# Kinen_Port.net
KiCad netlist of a schematic drawn in Altium Designer
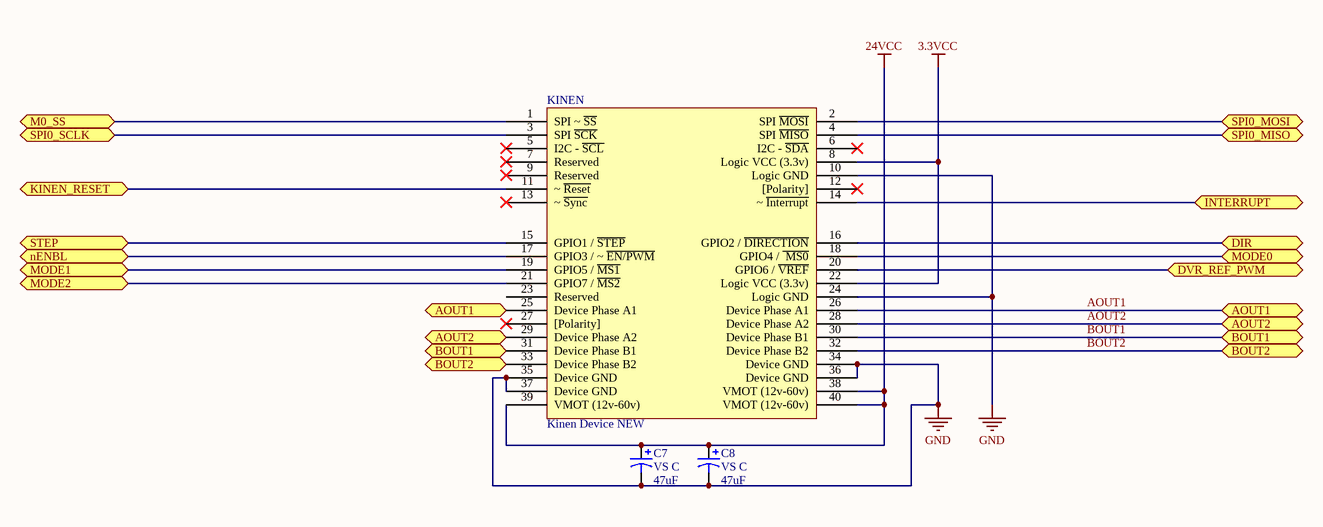
[diagram p0: Kinen Port.SchDoc]

(export (version "E")
  (design (tool "Eeschema 10.0.6"))
  (components
    (comp (ref "C7")
      (value "VS C")
      (footprint "Panasonic VS C")
      (description "Polarized Capacitor (Radial)")
      (fields (field (name "ALTIUM_VALUE") "47uF") (field (name "PUBLISHER") "Altium Limited"))
      (libsource (lib "Miscellaneous Devices") (part "Cap Pol1"))
    )
    (comp (ref "C8")
      (value "VS C")
      (footprint "Panasonic VS C")
      (description "Polarized Capacitor (Radial)")
      (fields (field (name "ALTIUM_VALUE") "47uF") (field (name "PUBLISHER") "Altium Limited"))
      (libsource (lib "Miscellaneous Devices") (part "Cap Pol1"))
    )
    (comp (ref "KINEN")
      (value "Kinen Device NEW")
      (footprint "Kinen Port - Device")
      (libsource (lib "ExtruderFinLib") (part "Kinen Device NEW"))
    )
  )
  (nets
    (net (code "1") (name "/AOUT1") (class "Default")
      (node (ref "KINEN") (pin "25") (pinfunction "Device_Phase_A1_25") (pintype "passive"))
      (node (ref "KINEN") (pin "26") (pinfunction "Device_Phase_A1_26") (pintype "passive"))
    )
    (net (code "2") (name "/AOUT2") (class "Default")
      (node (ref "KINEN") (pin "28") (pinfunction "Device_Phase_A2_28") (pintype "passive"))
      (node (ref "KINEN") (pin "29") (pinfunction "Device_Phase_A2_29") (pintype "passive"))
    )
    (net (code "3") (name "/BOUT1") (class "Default")
      (node (ref "KINEN") (pin "30") (pinfunction "Device_Phase_B1_30") (pintype "passive"))
      (node (ref "KINEN") (pin "31") (pinfunction "Device_Phase_B1_31") (pintype "passive"))
    )
    (net (code "4") (name "/BOUT2") (class "Default")
      (node (ref "KINEN") (pin "32") (pinfunction "Device_Phase_B2_32") (pintype "passive"))
      (node (ref "KINEN") (pin "33") (pinfunction "Device_Phase_B2_33") (pintype "passive"))
    )
    (net (code "5") (name "/DIR") (class "Default")
      (node (ref "KINEN") (pin "16") (pinfunction "GPIO2_/_~{DIRECTION}_16") (pintype "passive"))
    )
    (net (code "6") (name "/DVR_REF_PWM") (class "Default")
      (node (ref "KINEN") (pin "20") (pinfunction "GPIO6_/_~{VREF}_20") (pintype "passive"))
    )
    (net (code "7") (name "/INTERRUPT") (class "Default")
      (node (ref "KINEN") (pin "14") (pinfunction "~_~{Interrupt}_14") (pintype "passive"))
    )
    (net (code "8") (name "/KINEN_RESET") (class "Default")
      (node (ref "KINEN") (pin "11") (pinfunction "~_~{Reset}_11") (pintype "passive"))
    )
    (net (code "9") (name "/M0_SS") (class "Default")
      (node (ref "KINEN") (pin "1") (pinfunction "SPI_~_~{SS}_1") (pintype "passive"))
    )
    (net (code "10") (name "/MODE0") (class "Default")
      (node (ref "KINEN") (pin "18") (pinfunction "GPIO4_/_~{_MS0}_18") (pintype "passive"))
    )
    (net (code "11") (name "/MODE1") (class "Default")
      (node (ref "KINEN") (pin "19") (pinfunction "GPIO5_/_~{MS1}_19") (pintype "passive"))
    )
    (net (code "12") (name "/MODE2") (class "Default")
      (node (ref "KINEN") (pin "21") (pinfunction "GPIO7_/_~{MS2}_21") (pintype "passive"))
    )
    (net (code "13") (name "/SPI0_MISO") (class "Default")
      (node (ref "KINEN") (pin "4") (pinfunction "SPI_~{MISO}_4") (pintype "passive"))
    )
    (net (code "14") (name "/SPI0_MOSI") (class "Default")
      (node (ref "KINEN") (pin "2") (pinfunction "SPI_~{MOSI}_2") (pintype "passive"))
    )
    (net (code "15") (name "/SPI0_SCLK") (class "Default")
      (node (ref "KINEN") (pin "3") (pinfunction "SPI_~{SCK}_3") (pintype "passive"))
    )
    (net (code "16") (name "/STEP") (class "Default")
      (node (ref "KINEN") (pin "15") (pinfunction "GPIO1_/_~{STEP}_15") (pintype "passive"))
    )
    (net (code "17") (name "/nENBL") (class "Default")
      (node (ref "KINEN") (pin "17") (pinfunction "GPIO3_/_~_~{EN/PWM}_17") (pintype "passive"))
    )
    (net (code "18") (name "3.3VCC") (class "Default")
      (node (ref "KINEN") (pin "22") (pinfunction "Logic_VCC_(3.3v)_22") (pintype "passive"))
      (node (ref "KINEN") (pin "8") (pinfunction "Logic_VCC_(3.3v)_8") (pintype "passive"))
    )
    (net (code "19") (name "24VCC") (class "Default")
      (node (ref "C7") (pin "1") (pinfunction "1_1") (pintype "passive"))
      (node (ref "C8") (pin "1") (pinfunction "1_1") (pintype "passive"))
      (node (ref "KINEN") (pin "38") (pinfunction "VMOT_(12v-60v)_38") (pintype "passive"))
      (node (ref "KINEN") (pin "39") (pinfunction "VMOT_(12v-60v)_39") (pintype "passive"))
      (node (ref "KINEN") (pin "40") (pinfunction "VMOT_(12v-60v)_40") (pintype "passive"))
    )
    (net (code "20") (name "GND") (class "Default")
      (node (ref "C7") (pin "2") (pinfunction "2_2") (pintype "passive"))
      (node (ref "C8") (pin "2") (pinfunction "2_2") (pintype "passive"))
      (node (ref "KINEN") (pin "10") (pinfunction "Logic_GND_10") (pintype "passive"))
      (node (ref "KINEN") (pin "24") (pinfunction "Logic_GND_24") (pintype "passive"))
      (node (ref "KINEN") (pin "34") (pinfunction "Device_GND_34") (pintype "passive"))
      (node (ref "KINEN") (pin "35") (pinfunction "Device_GND_35") (pintype "passive"))
      (node (ref "KINEN") (pin "36") (pinfunction "Device_GND_36") (pintype "passive"))
      (node (ref "KINEN") (pin "37") (pinfunction "Device_GND_37") (pintype "passive"))
    )
    (net (code "21") (name "unconnected-(KINEN-I2C_-_~{SCL}-Pad5)") (class "Default")
      (node (ref "KINEN") (pin "5") (pinfunction "I2C_-_~{SCL}_5") (pintype "passive+no_connect"))
    )
    (net (code "22") (name "unconnected-(KINEN-I2C_-_~{SDA}-Pad6)") (class "Default")
      (node (ref "KINEN") (pin "6") (pinfunction "I2C_-_~{SDA}_6") (pintype "passive+no_connect"))
    )
    (net (code "23") (name "unconnected-(KINEN-Reserved-Pad7)") (class "Default")
      (node (ref "KINEN") (pin "7") (pinfunction "Reserved_7") (pintype "passive+no_connect"))
    )
    (net (code "24") (name "unconnected-(KINEN-Reserved-Pad9)") (class "Default")
      (node (ref "KINEN") (pin "9") (pinfunction "Reserved_9") (pintype "passive+no_connect"))
    )
    (net (code "25") (name "unconnected-(KINEN-Reserved-Pad23)") (class "Default")
      (node (ref "KINEN") (pin "23") (pinfunction "Reserved_23") (pintype "passive"))
    )
    (net (code "26") (name "unconnected-(KINEN-[Polarity]-Pad12)") (class "Default")
      (node (ref "KINEN") (pin "12") (pinfunction "[Polarity]_12") (pintype "passive+no_connect"))
    )
    (net (code "27") (name "unconnected-(KINEN-[Polarity]-Pad27)") (class "Default")
      (node (ref "KINEN") (pin "27") (pinfunction "[Polarity]_27") (pintype "passive+no_connect"))
    )
    (net (code "28") (name "unconnected-(KINEN-~_~{Sync}-Pad13)") (class "Default")
      (node (ref "KINEN") (pin "13") (pinfunction "~_~{Sync}_13") (pintype "passive+no_connect"))
    )
  )
)
